# STM32_Schematic.net
KiCad netlist of a schematic drawn in Altium Designer
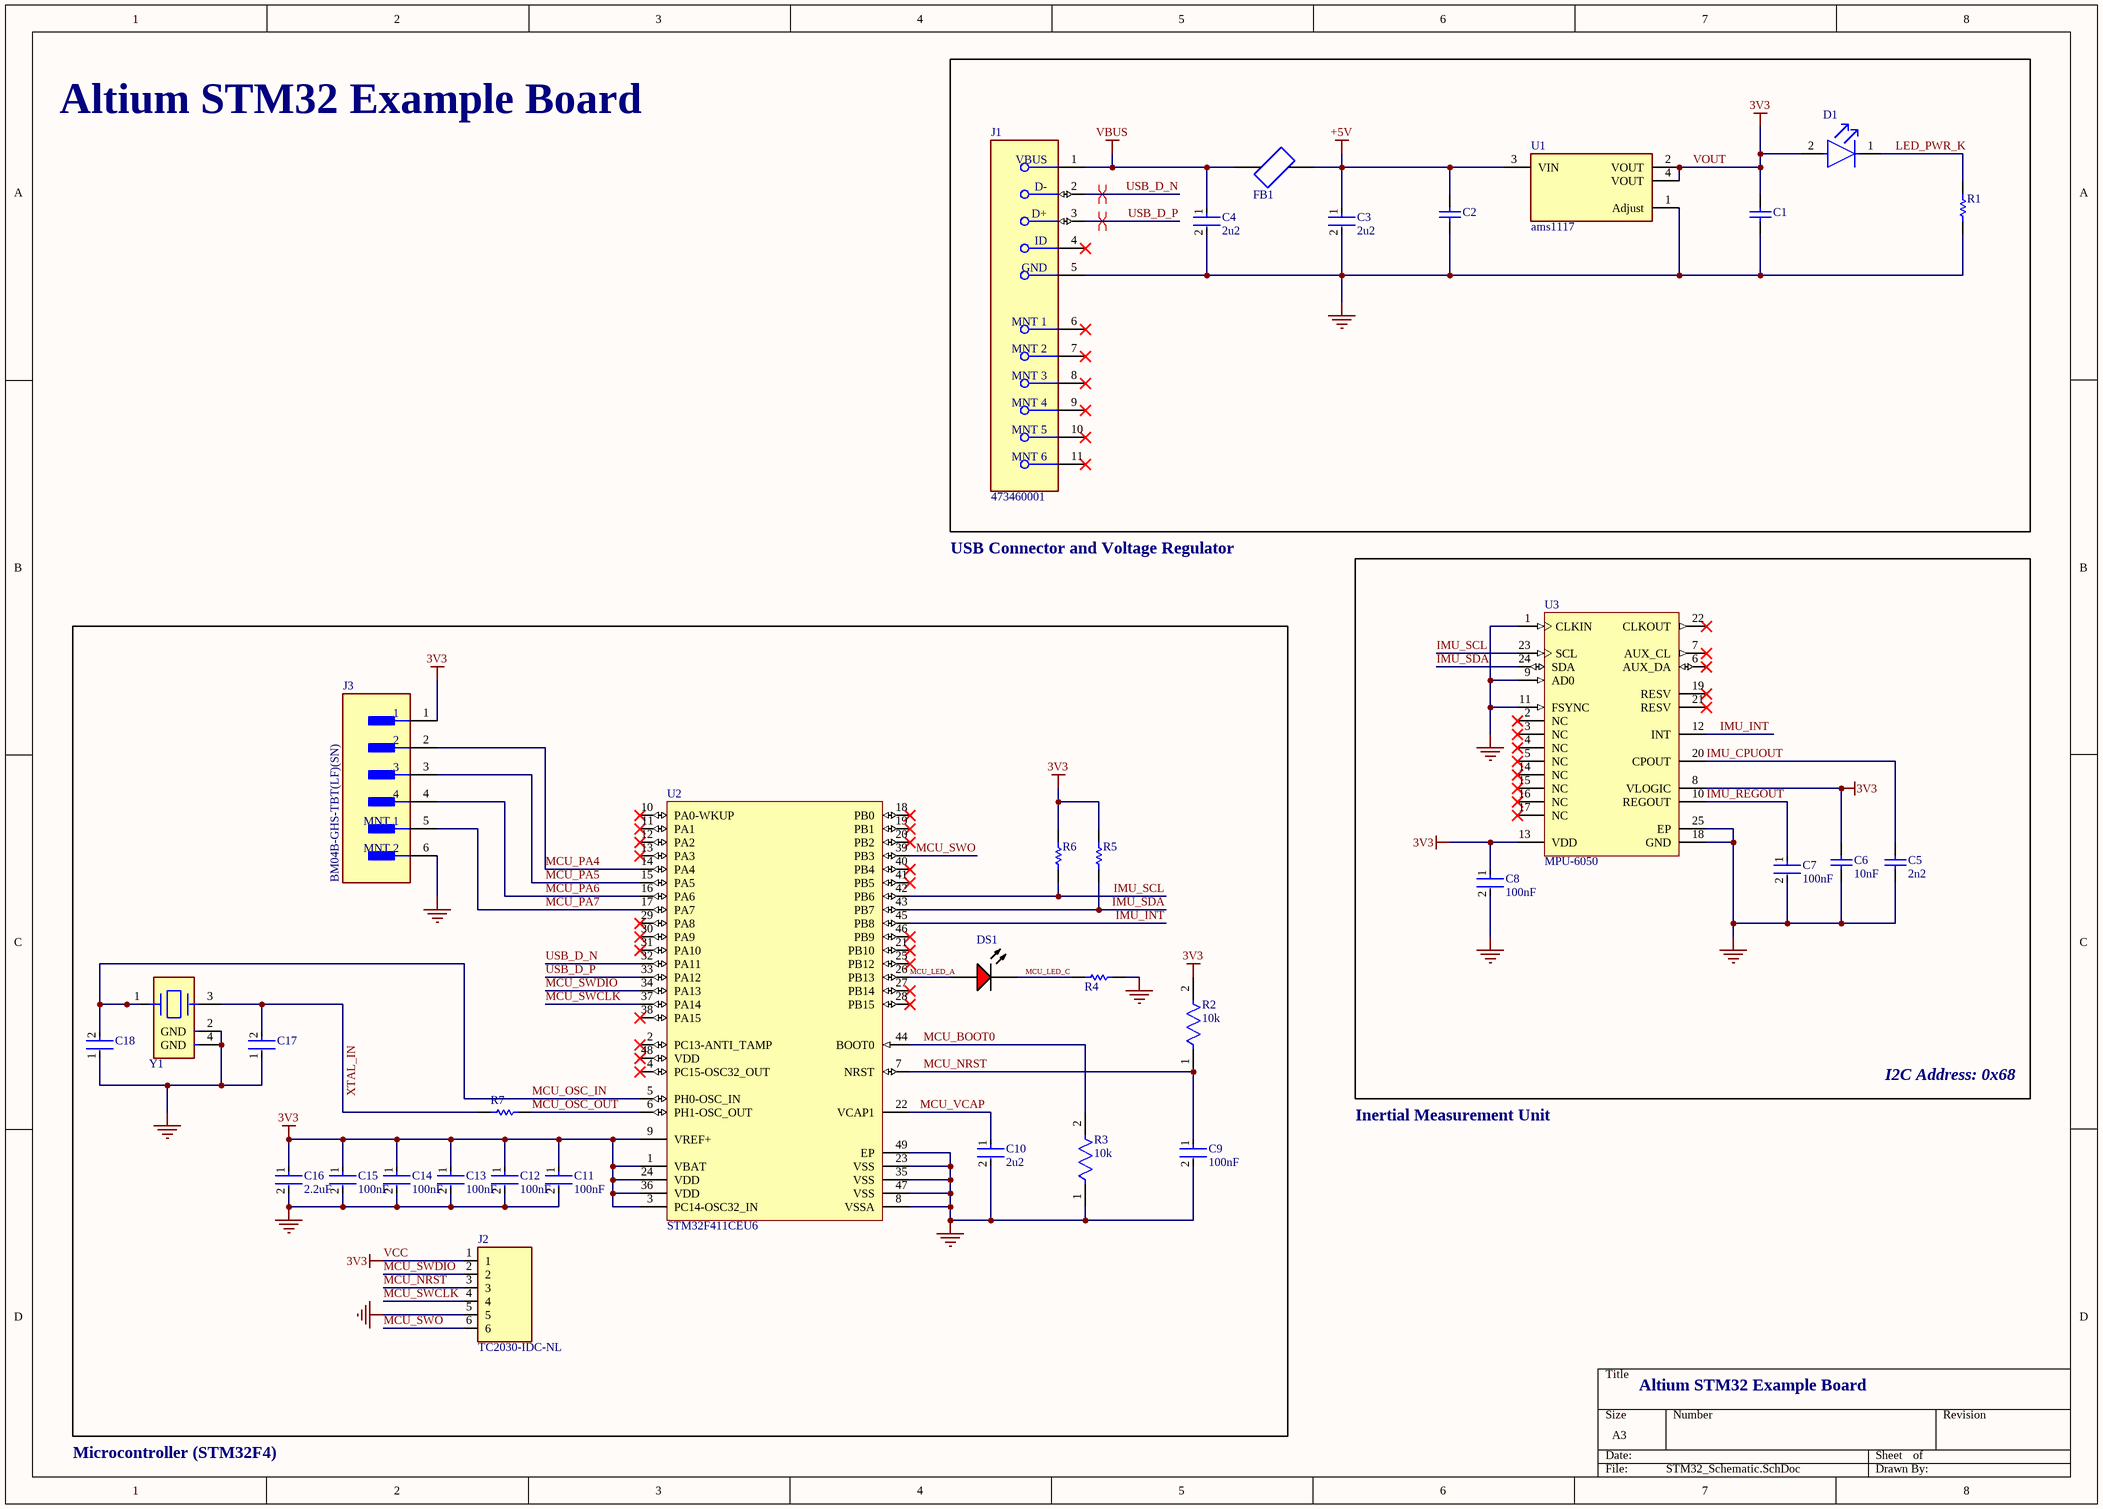
[diagram p0: STM32_Schematic.SchDoc]

(export (version "E")
  (design (tool "Eeschema 10.0.6"))
  (components
    (comp (ref "C1")
      (value "GRM32ER61C226KE20L")
      (footprint "MURA-1210_H_2.7_L")
      (fields (field (name "MANUFACTURER") "Murata") (field (name "TOLERANCE") "±10%"))
      (libsource (lib "Altium Content Vault") (part "CAP-NP-2"))
    )
    (comp (ref "C2")
      (value "GRM32ER61C226KE20L")
      (footprint "MURA-1210_H_2.7_L")
      (fields (field (name "MANUFACTURER") "Murata") (field (name "TOLERANCE") "±10%"))
      (libsource (lib "Altium Content Vault") (part "CAP-NP-2"))
    )
    (comp (ref "C3")
      (value "2u2")
      (footprint "FP-C3216-160-0_2-IPC_B")
      (description "Multilayer Ceramic Capacitors 2.2uF ±10% 100V X7S SMD 1206")
      (fields (field (name "TOLERANCE") "10%") (field (name "VOLTAGE") "100V"))
      (libsource (lib "Altium Content Vault") (part "11868f565c42a9108669ba33697ecf6"))
    )
    (comp (ref "C4")
      (value "2u2")
      (footprint "FP-C3216-160-0_2-IPC_B")
      (description "Multilayer Ceramic Capacitors 2.2uF ±10% 100V X7S SMD 1206")
      (fields (field (name "TOLERANCE") "10%") (field (name "VOLTAGE") "100V"))
      (libsource (lib "Altium Content Vault") (part "11868f565c42a9108669ba33697ecf6"))
    )
    (comp (ref "C5")
      (value "2n2")
      (footprint "CAPC2013X94X50LL20T25")
      (fields
        (field (name "PART NUMBER") "08051C222JAT2A")
        (field (name "MANUFACTURER") "AVX Interconnect / Elco")
      )
      (libsource (lib "Altium Content Vault") (part "CAP"))
    )
    (comp (ref "C6")
      (value "10nF")
      (footprint "CAPC1608X90X35ML10T15")
      (description "Chip Capacitor, 10 nF, +/- 10%, 50 V, -55 to 125 degC, 0603 (1608 Metric), RoHS, Tape and Reel")
      (fields (field (name "VOLTAGE") "50V") (field (name "TOLERANCE") "10%"))
      (libsource (lib "Altium Content Vault") (part "CAP-NP-2"))
    )
    (comp (ref "C7")
      (value "100nF")
      (footprint "FP-0805-L_2_01_0_2-W_1_25-IPC_B")
      (description "Automotive Ceramic Capacitor, 0805, 100nF, 10%, X7R, 15%, 100V")
      (fields (field (name "TOLERANCE") "10%") (field (name "VOLTAGE") "100V"))
      (libsource (lib "Altium Content Vault") (part "b4654b650e69147ec39a6b967a45e02"))
    )
    (comp (ref "C8")
      (value "100nF")
      (footprint "FP-0805-L_2_01_0_2-W_1_25-IPC_B")
      (description "Automotive Ceramic Capacitor, 0805, 100nF, 10%, X7R, 15%, 100V")
      (fields (field (name "TOLERANCE") "10%") (field (name "VOLTAGE") "100V"))
      (libsource (lib "Altium Content Vault") (part "b4654b650e69147ec39a6b967a45e02"))
    )
    (comp (ref "C9")
      (value "100nF")
      (footprint "FP-0805-L_2_01_0_2-W_1_25-IPC_B")
      (description "Automotive Ceramic Capacitor, 0805, 100nF, 10%, X7R, 15%, 100V")
      (fields (field (name "TOLERANCE") "10%") (field (name "VOLTAGE") "100V"))
      (libsource (lib "Altium Content Vault") (part "b4654b650e69147ec39a6b967a45e02"))
    )
    (comp (ref "C10")
      (value "2u2")
      (footprint "FP-C3216-160-0_2-IPC_B")
      (description "Multilayer Ceramic Capacitors 2.2uF ±10% 100V X7S SMD 1206")
      (fields (field (name "TOLERANCE") "10%") (field (name "VOLTAGE") "100V"))
      (libsource (lib "Altium Content Vault") (part "11868f565c42a9108669ba33697ecf6"))
    )
    (comp (ref "C11")
      (value "100nF")
      (footprint "FP-C0402-BB-MFG")
      (description "CAP CER 0.1UF 16V 5% X7R 0402")
      (fields
        (field (name "MANUFACTURER") "Kemet")
        (field (name "MANUFACTURER PART NUMBER") "C0402C104J4RACTU")
      )
      (libsource (lib "Altium Content Vault") (part "b4654b650e69147ec39a6b967a45e02"))
    )
    (comp (ref "C12")
      (value "100nF")
      (footprint "FP-C0402-BB-MFG")
      (description "CAP CER 0.1UF 16V 5% X7R 0402")
      (fields
        (field (name "MANUFACTURER") "Kemet")
        (field (name "MANUFACTURER PART NUMBER") "C0402C104J4RACTU")
      )
      (libsource (lib "Altium Content Vault") (part "b4654b650e69147ec39a6b967a45e02"))
    )
    (comp (ref "C13")
      (value "100nF")
      (footprint "FP-C0402-BB-MFG")
      (description "CAP CER 0.1UF 16V 5% X7R 0402")
      (fields
        (field (name "MANUFACTURER") "Kemet")
        (field (name "MANUFACTURER PART NUMBER") "C0402C104J4RACTU")
      )
      (libsource (lib "Altium Content Vault") (part "b4654b650e69147ec39a6b967a45e02"))
    )
    (comp (ref "C14")
      (value "100nF")
      (footprint "FP-C0402-BB-MFG")
      (description "CAP CER 0.1UF 16V 5% X7R 0402")
      (fields
        (field (name "MANUFACTURER") "Kemet")
        (field (name "MANUFACTURER PART NUMBER") "C0402C104J4RACTU")
      )
      (libsource (lib "Altium Content Vault") (part "b4654b650e69147ec39a6b967a45e02"))
    )
    (comp (ref "C15")
      (value "100nF")
      (footprint "FP-C0402-BB-MFG")
      (description "CAP CER 0.1UF 16V 5% X7R 0402")
      (fields
        (field (name "MANUFACTURER") "Kemet")
        (field (name "MANUFACTURER PART NUMBER") "C0402C104J4RACTU")
      )
      (libsource (lib "Altium Content Vault") (part "b4654b650e69147ec39a6b967a45e02"))
    )
    (comp (ref "C16")
      (value "2.2uF")
      (footprint "FP-C3216-160-0_2-IPC_B")
      (description "Multilayer Ceramic Capacitors 2.2uF ±10% 100V X7S SMD 1206")
      (fields (field (name "TOLERANCE") "10%") (field (name "VOLTAGE") "100V"))
      (libsource (lib "Altium Content Vault") (part "11868f565c42a9108669ba33697ecf6"))
    )
    (comp (ref "C17")
      (value "C1608C0G1H100D080AA")
      (footprint "FP-C1608-080-0_1-IPC_C")
      (description "Multilayer Ceramic Capacitors 10pF ±0.5pF 50V C0G SMD 0603")
      (fields (field (name "VOLTAGE") "50V") (field (name "TOLERANCE") "5%"))
      (libsource (lib "Altium Content Vault") (part "236180d848d6139a670b325ea6854c9"))
    )
    (comp (ref "C18")
      (value "C1608C0G1H100D080AA")
      (footprint "FP-C1608-080-0_1-IPC_C")
      (description "Multilayer Ceramic Capacitors 10pF ±0.5pF 50V C0G SMD 0603")
      (fields (field (name "VOLTAGE") "50V") (field (name "TOLERANCE") "5%"))
      (libsource (lib "Altium Content Vault") (part "236180d848d6139a670b325ea6854c9"))
    )
    (comp (ref "D1")
      (value "LTST-C190GKT")
      (footprint "FP-LTST-C190GKT-MFG")
      (description "LED GREEN CLEAR CHIP SMD")
      (fields (field (name "VOLTAGE") "2V"))
      (libsource (lib "Altium Content Vault") (part "8706943c75ba83719d021d2fdc84c58"))
    )
    (comp (ref "DS1")
      (value "TLMS1100-GS08")
      (footprint "VISH-TLMX1100_V")
      (description "LED, RED, 2.1 V, -40 to 100 degC, 2-Pin SMD (0603), RoHS, Tape and Reel")
      (fields (field (name "TOLERANCE") "5%"))
      (libsource (lib "Altium Content Vault") (part "LED-RED-AK-2"))
    )
    (comp (ref "FB1")
      (value "FBMH1608HL300-T")
      (footprint "BEADC1608X90N")
      (description "FERRITE BEAD, 0.028OHM, 2.5A, 0603, FULL REEL")
      (libsource (lib "Vellore Institute of Technology, Chennai") (part "FBMH1608HL300-T"))
    )
    (comp (ref "J1")
      (value "473460001")
      (footprint "FP-473460001-MFG")
      (description "CONN RCPT USB2.0 MICRO B SMD R/A")
      (fields
        (field (name "OCTOPART") "https://octopart.com/47346-0001-molex-7164928")
        (field (name "MANUFACTURER") "Molex")
      )
      (libsource (lib "Altium Content Vault") (part "53ae1f1d9b557310b43ca686e5bb76a"))
    )
    (comp (ref "J2")
      (value "TC2030-IDC-NL")
      (footprint "TAG_TC2030-IDC-NL")
      (description "CABLE ADAPTER 6 POS")
      (libsource (lib "Vellore Institute of Technology, Chennai") (part "TC2030-IDC-NL"))
    )
    (comp (ref "J3")
      (value "BM04B-GHS-TBT(LF)(SN)")
      (footprint "FP-BM04B-GHS-TBT_LF_SN-MFG")
      (description "CONN HEADER SMD 4POS 1.25MM")
      (libsource (lib "Altium Content Vault") (part "8e3688c4b118bffc0dd9b7401e414ba"))
    )
    (comp (ref "R1")
      (value "ERJ-6ENF1001V")
      (footprint "RESC2013X70X40ML20T20")
      (description "Chip Resistor, 1 KOhm, +/- 1%, 0.125 W, -55 to 155 degC, 0805 (2012 Metric), RoHS, Tape and Reel")
      (fields (field (name "MANUFACTURER") "Panasonic"))
      (libsource (lib "Altium Content Vault") (part "RES-2"))
    )
    (comp (ref "R2")
      (value "10k")
      (footprint "FP-MCT0603-IPC_C")
      (description "RES SMD 100 OHM 1% 1/8W 0603")
      (fields (field (name "TOLERANCE") "1%"))
      (libsource (lib "Altium Content Vault") (part "1029c3af85768c4190bb7ad29bc67b5"))
    )
    (comp (ref "R3")
      (value "10k")
      (footprint "FP-MCT0603-IPC_C")
      (description "RES SMD 100 OHM 1% 1/8W 0603")
      (fields (field (name "TOLERANCE") "1%"))
      (libsource (lib "Altium Content Vault") (part "1029c3af85768c4190bb7ad29bc67b5"))
    )
    (comp (ref "R4")
      (value "ERJ-6ENF1001V")
      (footprint "RESC2013X70X40ML20T20")
      (description "Chip Resistor, 1 KOhm, +/- 1%, 0.125 W, -55 to 155 degC, 0805 (2012 Metric), RoHS, Tape and Reel")
      (fields (field (name "MANUFACTURER") "Panasonic"))
      (libsource (lib "Altium Content Vault") (part "RES-2"))
    )
    (comp (ref "R5")
      (value "ERJ-2RKF2201X")
      (footprint "RESC1005X40X25LL05T05")
      (fields (field (name "MANUFACTURER") "Panasonic"))
      (libsource (lib "Altium Content Vault") (part "RES-2"))
    )
    (comp (ref "R6")
      (value "ERJ-2RKF2201X")
      (footprint "RESC1005X40X25LL05T05")
      (fields (field (name "MANUFACTURER") "Panasonic"))
      (libsource (lib "Altium Content Vault") (part "RES-2"))
    )
    (comp (ref "R7")
      (value "CRG0805ZR")
      (footprint "RESC2013X65X40LL15T20")
      (description "Chip Resistor, 0 Ohm, 0.125 W, -55 to 125 degC, 0805 (2012 Metric), RoHS, Tape and Reel")
      (fields (field (name "TOLERANCE") "0%") (field (name "MANUFACTURER") "TE Connectivity"))
      (libsource (lib "Altium Content Vault") (part "RES-2"))
    )
    (comp (ref "U1")
      (value "ams1117")
      (footprint "FP-ams1117-IPC_C")
      (description "1A LOW DROPOUT VOLTAGE REGULATOR")
      (libsource (lib "Altium Content Vault") (part "59ad430b93a2c51b3e6ee7c3b069677"))
    )
    (comp (ref "U2")
      (value "STM32F411CEU6")
      (footprint "STM-UFQFPN48_L")
      (libsource (lib "Altium Content Vault") (part "MC-ARM-STM32F411-UFQFPN48"))
    )
    (comp (ref "U3")
      (value "MPU-6050")
      (footprint "IS-QFN-24_V")
      (fields (field (name "MANUFACTURER") "InvenSense"))
      (libsource (lib "Altium Content Vault") (part "IS-MPU-6050-QFN-24"))
    )
    (comp (ref "Y1")
      (value "7M-24.000MEEQ-T")
      (footprint "FP-7M-MFG")
      (description "Crystal 24MHz, 10ppm, 10pF, 50Ω")
      (fields (field (name "TOLERANCE") "10ppm"))
      (libsource (lib "Altium Content Vault") (part "41079aabb0e87794b56622915be14ed"))
    )
  )
  (nets
    (net (code "1") (name "+5V") (class "Default")
      (node (ref "C2") (pin "1") (pinfunction "1_1") (pintype "passive"))
      (node (ref "C3") (pin "1") (pinfunction "1_1") (pintype "passive"))
      (node (ref "FB1") (pin "2") (pinfunction "2_2") (pintype "passive"))
      (node (ref "U1") (pin "3") (pinfunction "VIN_3") (pintype "power_in"))
    )
    (net (code "2") (name "/IMU_CPUOUT") (class "Default")
      (node (ref "C5") (pin "2") (pinfunction "2_2") (pintype "passive"))
      (node (ref "U3") (pin "20") (pinfunction "CPOUT_20") (pintype "passive"))
    )
    (net (code "3") (name "/IMU_INT") (class "Default")
      (node (ref "U2") (pin "45") (pinfunction "PB8_45") (pintype "bidirectional"))
      (node (ref "U3") (pin "12") (pinfunction "INT_12") (pintype "open_collector"))
    )
    (net (code "4") (name "/IMU_REGOUT") (class "Default")
      (node (ref "C7") (pin "1") (pinfunction "1_1") (pintype "passive"))
      (node (ref "U3") (pin "10") (pinfunction "REGOUT_10") (pintype "passive"))
    )
    (net (code "5") (name "/IMU_SCL") (class "Default")
      (node (ref "R6") (pin "1") (pinfunction "1_1") (pintype "passive"))
      (node (ref "U2") (pin "42") (pinfunction "PB6_42") (pintype "bidirectional"))
      (node (ref "U3") (pin "23") (pinfunction "SCL_23") (pintype "input"))
    )
    (net (code "6") (name "/IMU_SDA") (class "Default")
      (node (ref "R5") (pin "1") (pinfunction "1_1") (pintype "passive"))
      (node (ref "U2") (pin "43") (pinfunction "PB7_43") (pintype "bidirectional"))
      (node (ref "U3") (pin "24") (pinfunction "SDA_24") (pintype "bidirectional"))
    )
    (net (code "7") (name "/LED_PWR_K") (class "Default")
      (node (ref "D1") (pin "1") (pinfunction "C_1") (pintype "passive"))
      (node (ref "R1") (pin "2") (pinfunction "2_2") (pintype "passive"))
    )
    (net (code "8") (name "/MCU_BOOT0") (class "Default")
      (node (ref "R3") (pin "2") (pinfunction "2_2") (pintype "passive"))
      (node (ref "U2") (pin "44") (pinfunction "BOOT0_44") (pintype "input"))
    )
    (net (code "9") (name "/MCU_LED_A") (class "Default")
      (node (ref "DS1") (pin "1") (pinfunction "A_1") (pintype "passive"))
      (node (ref "U2") (pin "26") (pinfunction "PB13_26") (pintype "bidirectional"))
    )
    (net (code "10") (name "/MCU_LED_C") (class "Default")
      (node (ref "DS1") (pin "2") (pinfunction "K_2") (pintype "passive"))
      (node (ref "R4") (pin "1") (pinfunction "1_1") (pintype "passive"))
    )
    (net (code "11") (name "/MCU_NRST") (class "Default")
      (node (ref "C9") (pin "1") (pinfunction "1_1") (pintype "passive"))
      (node (ref "J2") (pin "3") (pinfunction "3_3") (pintype "passive"))
      (node (ref "R2") (pin "1") (pinfunction "1_1") (pintype "passive"))
      (node (ref "U2") (pin "7") (pinfunction "NRST_7") (pintype "bidirectional"))
    )
    (net (code "12") (name "/MCU_OSC_IN") (class "Default")
      (node (ref "C18") (pin "2") (pinfunction "2_2") (pintype "passive"))
      (node (ref "U2") (pin "5") (pinfunction "PH0-OSC_IN_5") (pintype "bidirectional"))
      (node (ref "Y1") (pin "1") (pinfunction "1_1") (pintype "passive"))
    )
    (net (code "13") (name "/MCU_OSC_OUT") (class "Default")
      (node (ref "R7") (pin "2") (pinfunction "2_2") (pintype "passive"))
      (node (ref "U2") (pin "6") (pinfunction "PH1-OSC_OUT_6") (pintype "bidirectional"))
    )
    (net (code "14") (name "/MCU_PA4") (class "Default")
      (node (ref "J3") (pin "2") (pinfunction "2_2") (pintype "passive"))
      (node (ref "U2") (pin "14") (pinfunction "PA4_14") (pintype "bidirectional"))
    )
    (net (code "15") (name "/MCU_PA5") (class "Default")
      (node (ref "J3") (pin "3") (pinfunction "3_3") (pintype "passive"))
      (node (ref "U2") (pin "15") (pinfunction "PA5_15") (pintype "bidirectional"))
    )
    (net (code "16") (name "/MCU_PA6") (class "Default")
      (node (ref "J3") (pin "4") (pinfunction "4_4") (pintype "passive"))
      (node (ref "U2") (pin "16") (pinfunction "PA6_16") (pintype "bidirectional"))
    )
    (net (code "17") (name "/MCU_PA7") (class "Default")
      (node (ref "J3") (pin "5") (pinfunction "MNT_1_5") (pintype "passive"))
      (node (ref "U2") (pin "17") (pinfunction "PA7_17") (pintype "bidirectional"))
    )
    (net (code "18") (name "/MCU_SWCLK") (class "Default")
      (node (ref "J2") (pin "4") (pinfunction "4_4") (pintype "passive"))
      (node (ref "U2") (pin "37") (pinfunction "PA14_37") (pintype "bidirectional"))
    )
    (net (code "19") (name "/MCU_SWDIO") (class "Default")
      (node (ref "J2") (pin "2") (pinfunction "2_2") (pintype "passive"))
      (node (ref "U2") (pin "34") (pinfunction "PA13_34") (pintype "bidirectional"))
    )
    (net (code "20") (name "/MCU_SWO") (class "Default")
      (node (ref "J2") (pin "6") (pinfunction "6_6") (pintype "passive"))
      (node (ref "U2") (pin "39") (pinfunction "PB3_39") (pintype "bidirectional"))
    )
    (net (code "21") (name "/MCU_VCAP") (class "Default")
      (node (ref "C10") (pin "1") (pinfunction "1_1") (pintype "passive"))
      (node (ref "U2") (pin "22") (pinfunction "VCAP1_22") (pintype "passive"))
    )
    (net (code "22") (name "/USB_D_N") (class "Default")
      (node (ref "J1") (pin "2") (pinfunction "D-_2") (pintype "bidirectional"))
      (node (ref "U2") (pin "32") (pinfunction "PA11_32") (pintype "bidirectional"))
    )
    (net (code "23") (name "/USB_D_P") (class "Default")
      (node (ref "J1") (pin "3") (pinfunction "D+_3") (pintype "bidirectional"))
      (node (ref "U2") (pin "33") (pinfunction "PA12_33") (pintype "bidirectional"))
    )
    (net (code "24") (name "/XTAL_IN") (class "Default")
      (node (ref "C17") (pin "2") (pinfunction "2_2") (pintype "passive"))
      (node (ref "R7") (pin "1") (pinfunction "1_1") (pintype "passive"))
      (node (ref "Y1") (pin "3") (pinfunction "3_3") (pintype "passive"))
    )
    (net (code "25") (name "3V3") (class "Default")
      (node (ref "C1") (pin "1") (pinfunction "1_1") (pintype "passive"))
      (node (ref "C11") (pin "1") (pinfunction "1_1") (pintype "passive"))
      (node (ref "C12") (pin "1") (pinfunction "1_1") (pintype "passive"))
      (node (ref "C13") (pin "1") (pinfunction "1_1") (pintype "passive"))
      (node (ref "C14") (pin "1") (pinfunction "1_1") (pintype "passive"))
      (node (ref "C15") (pin "1") (pinfunction "1_1") (pintype "passive"))
      (node (ref "C16") (pin "1") (pinfunction "1_1") (pintype "passive"))
      (node (ref "C6") (pin "2") (pinfunction "2_2") (pintype "passive"))
      (node (ref "C8") (pin "1") (pinfunction "1_1") (pintype "passive"))
      (node (ref "D1") (pin "2") (pinfunction "A_2") (pintype "passive"))
      (node (ref "J2") (pin "1") (pinfunction "1_1") (pintype "passive"))
      (node (ref "J3") (pin "1") (pinfunction "1_1") (pintype "passive"))
      (node (ref "R2") (pin "2") (pinfunction "2_2") (pintype "passive"))
      (node (ref "R5") (pin "2") (pinfunction "2_2") (pintype "passive"))
      (node (ref "R6") (pin "2") (pinfunction "2_2") (pintype "passive"))
      (node (ref "U1") (pin "2") (pinfunction "VOUT_2") (pintype "passive"))
      (node (ref "U1") (pin "4") (pinfunction "VOUT_4") (pintype "passive"))
      (node (ref "U2") (pin "1") (pinfunction "VBAT_1") (pintype "power_in"))
      (node (ref "U2") (pin "24") (pinfunction "VDD_24") (pintype "power_in"))
      (node (ref "U2") (pin "3") (pinfunction "PC14-OSC32_IN_3") (pintype "power_in"))
      (node (ref "U2") (pin "36") (pinfunction "VDD_36") (pintype "power_in"))
      (node (ref "U2") (pin "9") (pinfunction "VREF+_9") (pintype "power_in"))
      (node (ref "U3") (pin "13") (pinfunction "VDD_13") (pintype "power_in"))
      (node (ref "U3") (pin "8") (pinfunction "VLOGIC_8") (pintype "power_in"))
    )
    (net (code "26") (name "GND") (class "Default")
      (node (ref "C1") (pin "2") (pinfunction "2_2") (pintype "passive"))
      (node (ref "C10") (pin "2") (pinfunction "2_2") (pintype "passive"))
      (node (ref "C11") (pin "2") (pinfunction "2_2") (pintype "passive"))
      (node (ref "C12") (pin "2") (pinfunction "2_2") (pintype "passive"))
      (node (ref "C13") (pin "2") (pinfunction "2_2") (pintype "passive"))
      (node (ref "C14") (pin "2") (pinfunction "2_2") (pintype "passive"))
      (node (ref "C15") (pin "2") (pinfunction "2_2") (pintype "passive"))
      (node (ref "C16") (pin "2") (pinfunction "2_2") (pintype "passive"))
      (node (ref "C17") (pin "1") (pinfunction "1_1") (pintype "passive"))
      (node (ref "C18") (pin "1") (pinfunction "1_1") (pintype "passive"))
      (node (ref "C2") (pin "2") (pinfunction "2_2") (pintype "passive"))
      (node (ref "C3") (pin "2") (pinfunction "2_2") (pintype "passive"))
      (node (ref "C4") (pin "2") (pinfunction "2_2") (pintype "passive"))
      (node (ref "C5") (pin "1") (pinfunction "1_1") (pintype "passive"))
      (node (ref "C6") (pin "1") (pinfunction "1_1") (pintype "passive"))
      (node (ref "C7") (pin "2") (pinfunction "2_2") (pintype "passive"))
      (node (ref "C8") (pin "2") (pinfunction "2_2") (pintype "passive"))
      (node (ref "C9") (pin "2") (pinfunction "2_2") (pintype "passive"))
      (node (ref "J1") (pin "5") (pinfunction "GND_5") (pintype "power_in"))
      (node (ref "J2") (pin "5") (pinfunction "5_5") (pintype "passive"))
      (node (ref "J3") (pin "6") (pinfunction "MNT_2_6") (pintype "passive"))
      (node (ref "R1") (pin "1") (pinfunction "1_1") (pintype "passive"))
      (node (ref "R3") (pin "1") (pinfunction "1_1") (pintype "passive"))
      (node (ref "R4") (pin "2") (pinfunction "2_2") (pintype "passive"))
      (node (ref "U1") (pin "1") (pinfunction "Adjust_1") (pintype "passive"))
      (node (ref "U2") (pin "23") (pinfunction "VSS_23") (pintype "power_in"))
      (node (ref "U2") (pin "35") (pinfunction "VSS_35") (pintype "power_in"))
      (node (ref "U2") (pin "47") (pinfunction "VSS_47") (pintype "power_in"))
      (node (ref "U2") (pin "49") (pinfunction "EP_49") (pintype "power_in"))
      (node (ref "U2") (pin "8") (pinfunction "VSSA_8") (pintype "power_in"))
      (node (ref "U3") (pin "1") (pinfunction "CLKIN_1") (pintype "input"))
      (node (ref "U3") (pin "11") (pinfunction "FSYNC_11") (pintype "input"))
      (node (ref "U3") (pin "18") (pinfunction "GND_18") (pintype "power_in"))
      (node (ref "U3") (pin "25") (pinfunction "EP_25") (pintype "power_in"))
      (node (ref "U3") (pin "9") (pinfunction "AD0_9") (pintype "input"))
      (node (ref "Y1") (pin "2") (pinfunction "GND_2") (pintype "power_in"))
      (node (ref "Y1") (pin "4") (pinfunction "GND_4") (pintype "power_in"))
    )
    (net (code "27") (name "VBUS") (class "Default")
      (node (ref "C4") (pin "1") (pinfunction "1_1") (pintype "passive"))
      (node (ref "FB1") (pin "1") (pinfunction "1_1") (pintype "passive"))
      (node (ref "J1") (pin "1") (pinfunction "VBUS_1") (pintype "power_in"))
    )
    (net (code "28") (name "unconnected-(J1-ID-Pad4)") (class "Default")
      (node (ref "J1") (pin "4") (pinfunction "ID_4") (pintype "passive+no_connect"))
    )
    (net (code "29") (name "unconnected-(J1-MNT_1-Pad6)") (class "Default")
      (node (ref "J1") (pin "6") (pinfunction "MNT_1_6") (pintype "passive+no_connect"))
    )
    (net (code "30") (name "unconnected-(J1-MNT_2-Pad7)") (class "Default")
      (node (ref "J1") (pin "7") (pinfunction "MNT_2_7") (pintype "passive+no_connect"))
    )
    (net (code "31") (name "unconnected-(J1-MNT_3-Pad8)") (class "Default")
      (node (ref "J1") (pin "8") (pinfunction "MNT_3_8") (pintype "passive+no_connect"))
    )
    (net (code "32") (name "unconnected-(J1-MNT_4-Pad9)") (class "Default")
      (node (ref "J1") (pin "9") (pinfunction "MNT_4_9") (pintype "passive+no_connect"))
    )
    (net (code "33") (name "unconnected-(J1-MNT_5-Pad10)") (class "Default")
      (node (ref "J1") (pin "10") (pinfunction "MNT_5_10") (pintype "passive+no_connect"))
    )
    (net (code "34") (name "unconnected-(J1-MNT_6-Pad11)") (class "Default")
      (node (ref "J1") (pin "11") (pinfunction "MNT_6_11") (pintype "passive+no_connect"))
    )
    (net (code "35") (name "unconnected-(U2-PA0-WKUP-Pad10)") (class "Default")
      (node (ref "U2") (pin "10") (pinfunction "PA0-WKUP_10") (pintype "bidirectional+no_connect"))
    )
    (net (code "36") (name "unconnected-(U2-PA1-Pad11)") (class "Default")
      (node (ref "U2") (pin "11") (pinfunction "PA1_11") (pintype "bidirectional+no_connect"))
    )
    (net (code "37") (name "unconnected-(U2-PA2-Pad12)") (class "Default")
      (node (ref "U2") (pin "12") (pinfunction "PA2_12") (pintype "bidirectional+no_connect"))
    )
    (net (code "38") (name "unconnected-(U2-PA3-Pad13)") (class "Default")
      (node (ref "U2") (pin "13") (pinfunction "PA3_13") (pintype "bidirectional+no_connect"))
    )
    (net (code "39") (name "unconnected-(U2-PA8-Pad29)") (class "Default")
      (node (ref "U2") (pin "29") (pinfunction "PA8_29") (pintype "bidirectional+no_connect"))
    )
    (net (code "40") (name "unconnected-(U2-PA9-Pad30)") (class "Default")
      (node (ref "U2") (pin "30") (pinfunction "PA9_30") (pintype "bidirectional+no_connect"))
    )
    (net (code "41") (name "unconnected-(U2-PA10-Pad31)") (class "Default")
      (node (ref "U2") (pin "31") (pinfunction "PA10_31") (pintype "bidirectional+no_connect"))
    )
    (net (code "42") (name "unconnected-(U2-PA15-Pad38)") (class "Default")
      (node (ref "U2") (pin "38") (pinfunction "PA15_38") (pintype "bidirectional+no_connect"))
    )
    (net (code "43") (name "unconnected-(U2-PB0-Pad18)") (class "Default")
      (node (ref "U2") (pin "18") (pinfunction "PB0_18") (pintype "bidirectional+no_connect"))
    )
    (net (code "44") (name "unconnected-(U2-PB1-Pad19)") (class "Default")
      (node (ref "U2") (pin "19") (pinfunction "PB1_19") (pintype "bidirectional+no_connect"))
    )
    (net (code "45") (name "unconnected-(U2-PB2-Pad20)") (class "Default")
      (node (ref "U2") (pin "20") (pinfunction "PB2_20") (pintype "bidirectional+no_connect"))
    )
    (net (code "46") (name "unconnected-(U2-PB4-Pad40)") (class "Default")
      (node (ref "U2") (pin "40") (pinfunction "PB4_40") (pintype "bidirectional+no_connect"))
    )
    (net (code "47") (name "unconnected-(U2-PB5-Pad41)") (class "Default")
      (node (ref "U2") (pin "41") (pinfunction "PB5_41") (pintype "bidirectional+no_connect"))
    )
    (net (code "48") (name "unconnected-(U2-PB9-Pad46)") (class "Default")
      (node (ref "U2") (pin "46") (pinfunction "PB9_46") (pintype "bidirectional+no_connect"))
    )
    (net (code "49") (name "unconnected-(U2-PB10-Pad21)") (class "Default")
      (node (ref "U2") (pin "21") (pinfunction "PB10_21") (pintype "bidirectional+no_connect"))
    )
    (net (code "50") (name "unconnected-(U2-PB12-Pad25)") (class "Default")
      (node (ref "U2") (pin "25") (pinfunction "PB12_25") (pintype "bidirectional+no_connect"))
    )
    (net (code "51") (name "unconnected-(U2-PB14-Pad27)") (class "Default")
      (node (ref "U2") (pin "27") (pinfunction "PB14_27") (pintype "bidirectional+no_connect"))
    )
    (net (code "52") (name "unconnected-(U2-PB15-Pad28)") (class "Default")
      (node (ref "U2") (pin "28") (pinfunction "PB15_28") (pintype "bidirectional+no_connect"))
    )
    (net (code "53") (name "unconnected-(U2-PC13-ANTI_TAMP-Pad2)") (class "Default")
      (node (ref "U2") (pin "2") (pinfunction "PC13-ANTI_TAMP_2") (pintype "bidirectional+no_connect"))
    )
    (net (code "54") (name "unconnected-(U2-PC15-OSC32_OUT-Pad4)") (class "Default")
      (node (ref "U2") (pin "4") (pinfunction "PC15-OSC32_OUT_4") (pintype "bidirectional+no_connect"))
    )
    (net (code "55") (name "unconnected-(U2-VDD-Pad48)") (class "Default")
      (node (ref "U2") (pin "48") (pinfunction "VDD_48") (pintype "bidirectional+no_connect"))
    )
    (net (code "56") (name "unconnected-(U3-AUX_CL-Pad7)") (class "Default")
      (node (ref "U3") (pin "7") (pinfunction "AUX_CL_7") (pintype "output+no_connect"))
    )
    (net (code "57") (name "unconnected-(U3-AUX_DA-Pad6)") (class "Default")
      (node (ref "U3") (pin "6") (pinfunction "AUX_DA_6") (pintype "bidirectional+no_connect"))
    )
    (net (code "58") (name "unconnected-(U3-CLKOUT-Pad22)") (class "Default")
      (node (ref "U3") (pin "22") (pinfunction "CLKOUT_22") (pintype "output+no_connect"))
    )
    (net (code "59") (name "unconnected-(U3-NC-Pad2)") (class "Default")
      (node (ref "U3") (pin "2") (pinfunction "NC_2") (pintype "passive+no_connect"))
    )
    (net (code "60") (name "unconnected-(U3-NC-Pad3)") (class "Default")
      (node (ref "U3") (pin "3") (pinfunction "NC_3") (pintype "passive+no_connect"))
    )
    (net (code "61") (name "unconnected-(U3-NC-Pad4)") (class "Default")
      (node (ref "U3") (pin "4") (pinfunction "NC_4") (pintype "passive+no_connect"))
    )
    (net (code "62") (name "unconnected-(U3-NC-Pad5)") (class "Default")
      (node (ref "U3") (pin "5") (pinfunction "NC_5") (pintype "passive+no_connect"))
    )
    (net (code "63") (name "unconnected-(U3-NC-Pad14)") (class "Default")
      (node (ref "U3") (pin "14") (pinfunction "NC_14") (pintype "passive+no_connect"))
    )
    (net (code "64") (name "unconnected-(U3-NC-Pad15)") (class "Default")
      (node (ref "U3") (pin "15") (pinfunction "NC_15") (pintype "passive+no_connect"))
    )
    (net (code "65") (name "unconnected-(U3-NC-Pad16)") (class "Default")
      (node (ref "U3") (pin "16") (pinfunction "NC_16") (pintype "passive+no_connect"))
    )
    (net (code "66") (name "unconnected-(U3-NC-Pad17)") (class "Default")
      (node (ref "U3") (pin "17") (pinfunction "NC_17") (pintype "passive+no_connect"))
    )
    (net (code "67") (name "unconnected-(U3-RESV-Pad19)") (class "Default")
      (node (ref "U3") (pin "19") (pinfunction "RESV_19") (pintype "passive+no_connect"))
    )
    (net (code "68") (name "unconnected-(U3-RESV-Pad21)") (class "Default")
      (node (ref "U3") (pin "21") (pinfunction "RESV_21") (pintype "passive+no_connect"))
    )
  )
)
